# 2015_AX12DUPLICATOR.net
KiCad netlist of a schematic drawn in Altium Designer
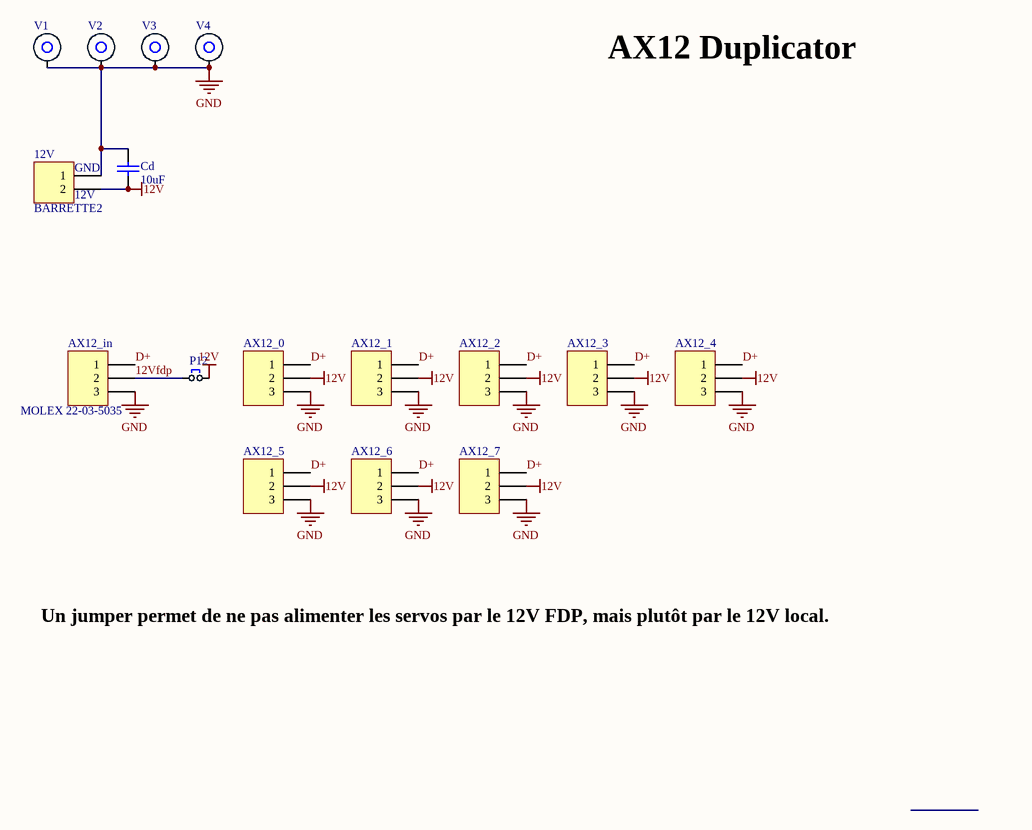
[diagram p0: 2015_AX12DUPLICATOR.SchDoc]

(export (version "E")
  (design (tool "Eeschema 10.0.6"))
  (components
    (comp (ref "12V")
      (value "BARRETTE2")
      (footprint "BORNIER2_HORIZ")
      (description "Header, 2-Pin")
      (fields (field (name "PUBLISHER") "Altium Limited"))
      (libsource (lib "Connecteur") (part "BARRETTE2"))
    )
    (comp (ref "AX12_0")
      (value "MOLEX 22-03-5035")
      (footprint "MOLEX3_2.5MM")
      (description "Header, 3-Pin")
      (fields (field (name "PUBLISHER") "Altium Limited"))
      (libsource (lib "Connecteur") (part "BARRETTE3"))
    )
    (comp (ref "AX12_1")
      (value "MOLEX 22-03-5035")
      (footprint "MOLEX3_2.5MM")
      (description "Header, 3-Pin")
      (fields (field (name "PUBLISHER") "Altium Limited"))
      (libsource (lib "Connecteur") (part "BARRETTE3"))
    )
    (comp (ref "AX12_2")
      (value "MOLEX 22-03-5035")
      (footprint "MOLEX3_2.5MM")
      (description "Header, 3-Pin")
      (fields (field (name "PUBLISHER") "Altium Limited"))
      (libsource (lib "Connecteur") (part "BARRETTE3"))
    )
    (comp (ref "AX12_3")
      (value "MOLEX 22-03-5035")
      (footprint "MOLEX3_2.5MM")
      (description "Header, 3-Pin")
      (fields (field (name "PUBLISHER") "Altium Limited"))
      (libsource (lib "Connecteur") (part "BARRETTE3"))
    )
    (comp (ref "AX12_4")
      (value "MOLEX 22-03-5035")
      (footprint "MOLEX3_2.5MM")
      (description "Header, 3-Pin")
      (fields (field (name "PUBLISHER") "Altium Limited"))
      (libsource (lib "Connecteur") (part "BARRETTE3"))
    )
    (comp (ref "AX12_5")
      (value "MOLEX 22-03-5035")
      (footprint "MOLEX3_2.5MM")
      (description "Header, 3-Pin")
      (fields (field (name "PUBLISHER") "Altium Limited"))
      (libsource (lib "Connecteur") (part "BARRETTE3"))
    )
    (comp (ref "AX12_6")
      (value "MOLEX 22-03-5035")
      (footprint "MOLEX3_2.5MM")
      (description "Header, 3-Pin")
      (fields (field (name "PUBLISHER") "Altium Limited"))
      (libsource (lib "Connecteur") (part "BARRETTE3"))
    )
    (comp (ref "AX12_7")
      (value "MOLEX 22-03-5035")
      (footprint "MOLEX3_2.5MM")
      (description "Header, 3-Pin")
      (fields (field (name "PUBLISHER") "Altium Limited"))
      (libsource (lib "Connecteur") (part "BARRETTE3"))
    )
    (comp (ref "AX12_in")
      (value "MOLEX 22-03-5035")
      (footprint "MOLEX3_2.5MM")
      (description "Header, 3-Pin")
      (fields (field (name "PUBLISHER") "Altium Limited"))
      (libsource (lib "Connecteur") (part "BARRETTE3"))
    )
    (comp (ref "Cd")
      (value "10uF")
      (footprint "C1206_N")
      (description "Capacitor")
      (fields (field (name "PUBLISHER") "Altium Limited"))
      (libsource (lib "_ROBOT") (part "Condensateur"))
    )
    (comp (ref "P12")
      (value "Jumper SIP 2.54")
      (footprint "HDR1X2")
      (description "Jumper SIP2.54")
      (libsource (lib "Connecteur") (part "Jumper SIP2.54"))
    )
    (comp (ref "V1")
      (value "Entretoise WURTH CMS")
      (footprint "ENTRETOISE_CMS")
      (description "Entretoise Wurth")
      (fields (field (name "PUBLISHER") "Damien Guitton"))
      (libsource (lib "_ROBOT") (part "Entretoise WURTH CMS"))
    )
    (comp (ref "V2")
      (value "Entretoise WURTH CMS")
      (footprint "ENTRETOISE_CMS")
      (description "Entretoise Wurth")
      (fields (field (name "PUBLISHER") "Damien Guitton"))
      (libsource (lib "_ROBOT") (part "Entretoise WURTH CMS"))
    )
    (comp (ref "V3")
      (value "Entretoise WURTH CMS")
      (footprint "ENTRETOISE_CMS")
      (description "Entretoise Wurth")
      (fields (field (name "PUBLISHER") "Damien Guitton"))
      (libsource (lib "_ROBOT") (part "Entretoise WURTH CMS"))
    )
    (comp (ref "V4")
      (value "Entretoise WURTH CMS")
      (footprint "ENTRETOISE_CMS")
      (description "Entretoise Wurth")
      (fields (field (name "PUBLISHER") "Damien Guitton"))
      (libsource (lib "_ROBOT") (part "Entretoise WURTH CMS"))
    )
  )
  (nets
    (net (code "1") (name "/12Vfdp") (class "Default")
      (node (ref "AX12_in") (pin "2") (pinfunction "2_2") (pintype "passive"))
      (node (ref "P12") (pin "1") (pinfunction "1_1") (pintype "passive"))
    )
    (net (code "2") (name "/D+") (class "Default")
      (node (ref "AX12_0") (pin "1") (pinfunction "1_1") (pintype "passive"))
      (node (ref "AX12_1") (pin "1") (pinfunction "1_1") (pintype "passive"))
      (node (ref "AX12_2") (pin "1") (pinfunction "1_1") (pintype "passive"))
      (node (ref "AX12_3") (pin "1") (pinfunction "1_1") (pintype "passive"))
      (node (ref "AX12_4") (pin "1") (pinfunction "1_1") (pintype "passive"))
      (node (ref "AX12_5") (pin "1") (pinfunction "1_1") (pintype "passive"))
      (node (ref "AX12_6") (pin "1") (pinfunction "1_1") (pintype "passive"))
      (node (ref "AX12_7") (pin "1") (pinfunction "1_1") (pintype "passive"))
      (node (ref "AX12_in") (pin "1") (pinfunction "1_1") (pintype "passive"))
    )
    (net (code "3") (name "12V") (class "Default")
      (node (ref "12V") (pin "2") (pinfunction "2_2") (pintype "passive"))
      (node (ref "AX12_0") (pin "2") (pinfunction "2_2") (pintype "passive"))
      (node (ref "AX12_1") (pin "2") (pinfunction "2_2") (pintype "passive"))
      (node (ref "AX12_2") (pin "2") (pinfunction "2_2") (pintype "passive"))
      (node (ref "AX12_3") (pin "2") (pinfunction "2_2") (pintype "passive"))
      (node (ref "AX12_4") (pin "2") (pinfunction "2_2") (pintype "passive"))
      (node (ref "AX12_5") (pin "2") (pinfunction "2_2") (pintype "passive"))
      (node (ref "AX12_6") (pin "2") (pinfunction "2_2") (pintype "passive"))
      (node (ref "AX12_7") (pin "2") (pinfunction "2_2") (pintype "passive"))
      (node (ref "Cd") (pin "1") (pinfunction "1_1") (pintype "passive"))
      (node (ref "P12") (pin "2") (pinfunction "2_2") (pintype "passive"))
    )
    (net (code "4") (name "GND") (class "Default")
      (node (ref "12V") (pin "1") (pinfunction "1_1") (pintype "passive"))
      (node (ref "AX12_0") (pin "3") (pinfunction "3_3") (pintype "passive"))
      (node (ref "AX12_1") (pin "3") (pinfunction "3_3") (pintype "passive"))
      (node (ref "AX12_2") (pin "3") (pinfunction "3_3") (pintype "passive"))
      (node (ref "AX12_3") (pin "3") (pinfunction "3_3") (pintype "passive"))
      (node (ref "AX12_4") (pin "3") (pinfunction "3_3") (pintype "passive"))
      (node (ref "AX12_5") (pin "3") (pinfunction "3_3") (pintype "passive"))
      (node (ref "AX12_6") (pin "3") (pinfunction "3_3") (pintype "passive"))
      (node (ref "AX12_7") (pin "3") (pinfunction "3_3") (pintype "passive"))
      (node (ref "AX12_in") (pin "3") (pinfunction "3_3") (pintype "passive"))
      (node (ref "Cd") (pin "2") (pinfunction "2_2") (pintype "passive"))
      (node (ref "V1") (pin "1") (pinfunction "1_1") (pintype "passive"))
      (node (ref "V2") (pin "1") (pinfunction "1_1") (pintype "passive"))
      (node (ref "V3") (pin "1") (pinfunction "1_1") (pintype "passive"))
      (node (ref "V4") (pin "1") (pinfunction "1_1") (pintype "passive"))
    )
  )
)
